# TauryCurrentSenseAmp.net
KiCad netlist of a schematic drawn in EAGLE
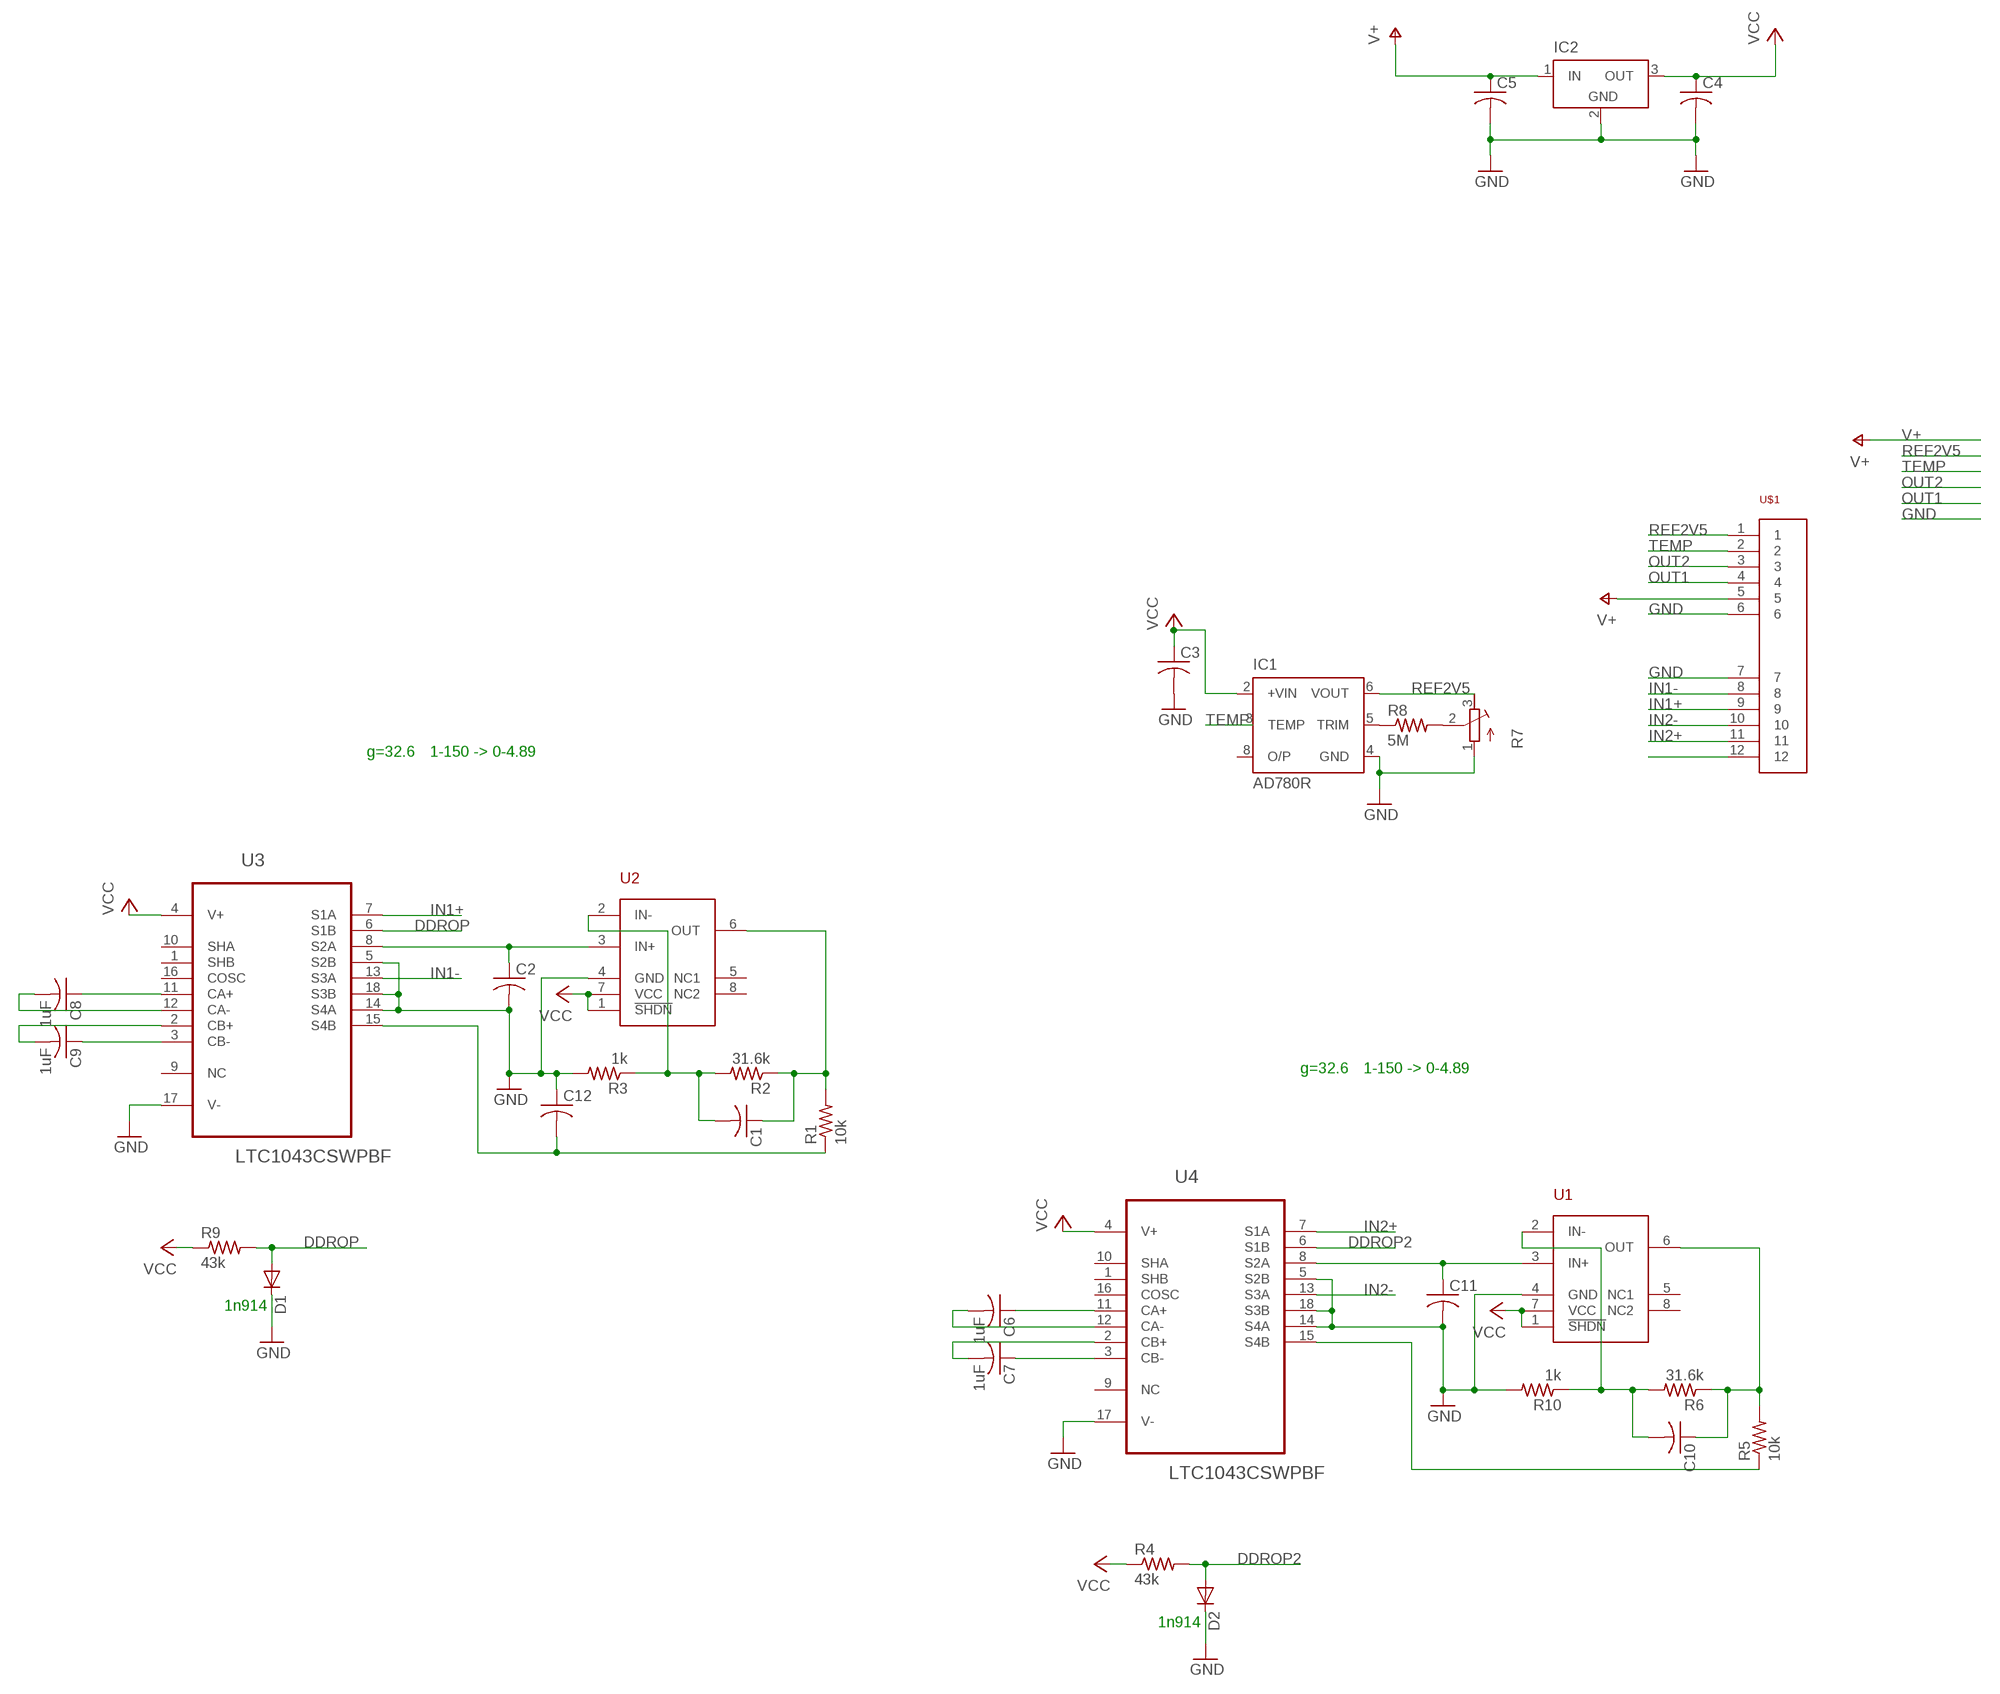
[diagram p0: schematic, sheet 1]

(export (version "E")
  (design (tool "Eeschema 10.0.6"))
  (components
    (comp (ref "C1")
      (value "C-USC0805")
      (footprint "eagle-import:C0805")
      (libsource (lib "eagle-import") (part "C-USC0805"))
    )
    (comp (ref "C2")
      (value "C-USC0805")
      (footprint "eagle-import:C0805")
      (libsource (lib "eagle-import") (part "C-USC0805"))
    )
    (comp (ref "C3")
      (value "C-USC0805")
      (footprint "eagle-import:C0805")
      (libsource (lib "eagle-import") (part "C-USC0805"))
    )
    (comp (ref "C4")
      (value "C-USC0805")
      (footprint "eagle-import:C0805")
      (libsource (lib "eagle-import") (part "C-USC0805"))
    )
    (comp (ref "C5")
      (value "C-USC0805")
      (footprint "eagle-import:C0805")
      (libsource (lib "eagle-import") (part "C-USC0805"))
    )
    (comp (ref "C6")
      (value "1uF")
      (footprint "eagle-import:C0805")
      (libsource (lib "eagle-import") (part "C-USC0805"))
    )
    (comp (ref "C7")
      (value "1uF")
      (footprint "eagle-import:C0805")
      (libsource (lib "eagle-import") (part "C-USC0805"))
    )
    (comp (ref "C8")
      (value "1uF")
      (footprint "eagle-import:C0805")
      (libsource (lib "eagle-import") (part "C-USC0805"))
    )
    (comp (ref "C9")
      (value "1uF")
      (footprint "eagle-import:C0805")
      (libsource (lib "eagle-import") (part "C-USC0805"))
    )
    (comp (ref "C10")
      (value "C-USC0805")
      (footprint "eagle-import:C0805")
      (libsource (lib "eagle-import") (part "C-USC0805"))
    )
    (comp (ref "C11")
      (value "C-USC0805")
      (footprint "eagle-import:C0805")
      (libsource (lib "eagle-import") (part "C-USC0805"))
    )
    (comp (ref "C12")
      (value "C-USC0805")
      (footprint "eagle-import:C0805")
      (libsource (lib "eagle-import") (part "C-USC0805"))
    )
    (comp (ref "D1")
      (value "DIODE-SOD323-R")
      (footprint "eagle-import:SOD323-R")
      (libsource (lib "eagle-import") (part "DIODE-SOD323-R"))
    )
    (comp (ref "D2")
      (value "DIODE-SOD523")
      (footprint "eagle-import:SOD523")
      (libsource (lib "eagle-import") (part "DIODE-SOD523"))
    )
    (comp (ref "IC1")
      (value "AD780R")
      (footprint "eagle-import:SO8")
      (fields (field (name "MPN") "AD780BRZ-REEL"))
      (libsource (lib "eagle-import") (part "AD780R"))
    )
    (comp (ref "IC2")
      (value "LT1129CST5")
      (footprint "eagle-import:SOT223")
      (fields (field (name "MPN") "LT1129CST-5#PBF"))
      (libsource (lib "eagle-import") (part "LT1129CST5"))
    )
    (comp (ref "R1")
      (value "10k")
      (footprint "eagle-import:R0805")
      (libsource (lib "eagle-import") (part "R-US_R0805"))
    )
    (comp (ref "R2")
      (value "31.6k")
      (footprint "eagle-import:R0805")
      (libsource (lib "eagle-import") (part "R-US_R0805"))
    )
    (comp (ref "R3")
      (value "1k")
      (footprint "eagle-import:R0805")
      (libsource (lib "eagle-import") (part "R-US_R0805"))
    )
    (comp (ref "R4")
      (value "43k")
      (footprint "eagle-import:R0805")
      (libsource (lib "eagle-import") (part "R-US_R0805"))
    )
    (comp (ref "R5")
      (value "10k")
      (footprint "eagle-import:R0805")
      (libsource (lib "eagle-import") (part "R-US_R0805"))
    )
    (comp (ref "R6")
      (value "31.6k")
      (footprint "eagle-import:R0805")
      (libsource (lib "eagle-import") (part "R-US_R0805"))
    )
    (comp (ref "R7")
      (value "R-TRIMM5W")
      (footprint "eagle-import:RTRIM5W")
      (libsource (lib "eagle-import") (part "R-TRIMM5W"))
    )
    (comp (ref "R8")
      (value "5M")
      (footprint "eagle-import:R0805")
      (libsource (lib "eagle-import") (part "R-US_R0805"))
    )
    (comp (ref "R9")
      (value "43k")
      (footprint "eagle-import:R0805")
      (libsource (lib "eagle-import") (part "R-US_R0805"))
    )
    (comp (ref "R10")
      (value "1k")
      (footprint "eagle-import:R0805")
      (libsource (lib "eagle-import") (part "R-US_R0805"))
    )
    (comp (ref "U$1")
      (value "DMB-4770")
      (footprint "eagle-import:DMB-4770-PCB")
      (libsource (lib "eagle-import") (part "DMB-4770"))
    )
    (comp (ref "U1")
      (value "MAX4239")
      (footprint "eagle-import:SO8")
      (libsource (lib "eagle-import") (part "MAX4239"))
    )
    (comp (ref "U2")
      (value "MAX4239")
      (footprint "eagle-import:SO8")
      (libsource (lib "eagle-import") (part "MAX4239"))
    )
    (comp (ref "U3")
      (value "LTC1043CSWPBF")
      (footprint "eagle-import:SOIC127P1032X264-18N")
      (fields (field (name "MPN") "LTC1043CSW#PBF"))
      (libsource (lib "eagle-import") (part "LTC1043CSWPBF"))
    )
    (comp (ref "U4")
      (value "LTC1043CSWPBF")
      (footprint "eagle-import:SOIC127P1032X264-18N")
      (fields (field (name "MPN") "LTC1043CSW#PBF"))
      (libsource (lib "eagle-import") (part "LTC1043CSWPBF"))
    )
  )
  (nets
    (net (code "1") (name "/DDROP") (class "Default")
      (node (ref "D1") (pin "A") (pinfunction "A_A") (pintype "passive"))
      (node (ref "R9") (pin "2") (pinfunction "2_2") (pintype "passive"))
      (node (ref "U3") (pin "6") (pinfunction "S1B_6") (pintype "passive"))
    )
    (net (code "2") (name "/DDROP2") (class "Default")
      (node (ref "D2") (pin "A") (pinfunction "A_A") (pintype "passive"))
      (node (ref "R4") (pin "2") (pinfunction "2_2") (pintype "passive"))
      (node (ref "U4") (pin "6") (pinfunction "S1B_6") (pintype "passive"))
    )
    (net (code "3") (name "/IN1+") (class "Default")
      (node (ref "U$1") (pin "9") (pinfunction "9_9") (pintype "bidirectional"))
      (node (ref "U3") (pin "7") (pinfunction "S1A_7") (pintype "passive"))
    )
    (net (code "4") (name "/IN1-") (class "Default")
      (node (ref "U$1") (pin "8") (pinfunction "8_8") (pintype "bidirectional"))
      (node (ref "U3") (pin "13") (pinfunction "S3A_13") (pintype "passive"))
    )
    (net (code "5") (name "/IN2+") (class "Default")
      (node (ref "U$1") (pin "11") (pinfunction "11_11") (pintype "bidirectional"))
      (node (ref "U4") (pin "7") (pinfunction "S1A_7") (pintype "passive"))
    )
    (net (code "6") (name "/IN2-") (class "Default")
      (node (ref "U$1") (pin "10") (pinfunction "10_10") (pintype "bidirectional"))
      (node (ref "U4") (pin "13") (pinfunction "S3A_13") (pintype "passive"))
    )
    (net (code "7") (name "/OUT1") (class "Default")
      (node (ref "C1") (pin "1") (pinfunction "1_1") (pintype "passive"))
      (node (ref "R1") (pin "2") (pinfunction "2_2") (pintype "passive"))
      (node (ref "R2") (pin "1") (pinfunction "1_1") (pintype "passive"))
      (node (ref "U$1") (pin "4") (pinfunction "4_4") (pintype "bidirectional"))
      (node (ref "U2") (pin "6") (pinfunction "OUT_6") (pintype "bidirectional"))
    )
    (net (code "8") (name "/OUT2") (class "Default")
      (node (ref "C10") (pin "1") (pinfunction "1_1") (pintype "passive"))
      (node (ref "R5") (pin "2") (pinfunction "2_2") (pintype "passive"))
      (node (ref "R6") (pin "1") (pinfunction "1_1") (pintype "passive"))
      (node (ref "U$1") (pin "3") (pinfunction "3_3") (pintype "bidirectional"))
      (node (ref "U1") (pin "6") (pinfunction "OUT_6") (pintype "bidirectional"))
    )
    (net (code "9") (name "/REF2V5") (class "Default")
      (node (ref "IC1") (pin "6") (pinfunction "VOUT_6") (pintype "input"))
      (node (ref "R7") (pin "3") (pinfunction "E_3") (pintype "passive"))
      (node (ref "U$1") (pin "1") (pinfunction "1_1") (pintype "bidirectional"))
    )
    (net (code "10") (name "/TEMP") (class "Default")
      (node (ref "IC1") (pin "3") (pinfunction "TEMP_3") (pintype "input"))
      (node (ref "U$1") (pin "2") (pinfunction "2_2") (pintype "bidirectional"))
    )
    (net (code "11") (name "GND") (class "Default")
      (node (ref "C11") (pin "2") (pinfunction "2_2") (pintype "passive"))
      (node (ref "C12") (pin "1") (pinfunction "1_1") (pintype "passive"))
      (node (ref "C2") (pin "2") (pinfunction "2_2") (pintype "passive"))
      (node (ref "C3") (pin "2") (pinfunction "2_2") (pintype "passive"))
      (node (ref "C4") (pin "2") (pinfunction "2_2") (pintype "passive"))
      (node (ref "C5") (pin "2") (pinfunction "2_2") (pintype "passive"))
      (node (ref "D1") (pin "C") (pinfunction "C_C") (pintype "passive"))
      (node (ref "D2") (pin "C") (pinfunction "C_C") (pintype "passive"))
      (node (ref "IC1") (pin "4") (pinfunction "GND_4") (pintype "power_in"))
      (node (ref "IC2") (pin "2") (pinfunction "GND_2") (pintype "power_in"))
      (node (ref "R10") (pin "2") (pinfunction "2_2") (pintype "passive"))
      (node (ref "R3") (pin "2") (pinfunction "2_2") (pintype "passive"))
      (node (ref "R7") (pin "1") (pinfunction "A_1") (pintype "passive"))
      (node (ref "U$1") (pin "6") (pinfunction "6_6") (pintype "bidirectional"))
      (node (ref "U$1") (pin "7") (pinfunction "7_7") (pintype "bidirectional"))
      (node (ref "U1") (pin "4") (pinfunction "GND_4") (pintype "bidirectional"))
      (node (ref "U2") (pin "4") (pinfunction "GND_4") (pintype "bidirectional"))
      (node (ref "U3") (pin "14") (pinfunction "S4A_14") (pintype "passive"))
      (node (ref "U3") (pin "17") (pinfunction "V-_17") (pintype "power_in"))
      (node (ref "U3") (pin "18") (pinfunction "S3B_18") (pintype "passive"))
      (node (ref "U3") (pin "5") (pinfunction "S2B_5") (pintype "passive"))
      (node (ref "U4") (pin "14") (pinfunction "S4A_14") (pintype "passive"))
      (node (ref "U4") (pin "17") (pinfunction "V-_17") (pintype "power_in"))
      (node (ref "U4") (pin "18") (pinfunction "S3B_18") (pintype "passive"))
      (node (ref "U4") (pin "5") (pinfunction "S2B_5") (pintype "passive"))
    )
    (net (code "12") (name "Net-(IC1-TRIM)") (class "Default")
      (node (ref "IC1") (pin "5") (pinfunction "TRIM_5") (pintype "input"))
      (node (ref "R8") (pin "1") (pinfunction "1_1") (pintype "passive"))
    )
    (net (code "13") (name "Net-(R7-S)") (class "Default")
      (node (ref "R7") (pin "2") (pinfunction "S_2") (pintype "passive"))
      (node (ref "R8") (pin "2") (pinfunction "2_2") (pintype "passive"))
    )
    (net (code "14") (name "Net-(U1-IN+)") (class "Default")
      (node (ref "C11") (pin "1") (pinfunction "1_1") (pintype "passive"))
      (node (ref "U1") (pin "3") (pinfunction "IN+_3") (pintype "bidirectional"))
      (node (ref "U4") (pin "8") (pinfunction "S2A_8") (pintype "passive"))
    )
    (net (code "15") (name "Net-(U1-IN-)") (class "Default")
      (node (ref "C10") (pin "2") (pinfunction "2_2") (pintype "passive"))
      (node (ref "R10") (pin "1") (pinfunction "1_1") (pintype "passive"))
      (node (ref "R6") (pin "2") (pinfunction "2_2") (pintype "passive"))
      (node (ref "U1") (pin "2") (pinfunction "IN-_2") (pintype "bidirectional"))
    )
    (net (code "16") (name "Net-(U2-IN+)") (class "Default")
      (node (ref "C2") (pin "1") (pinfunction "1_1") (pintype "passive"))
      (node (ref "U2") (pin "3") (pinfunction "IN+_3") (pintype "bidirectional"))
      (node (ref "U3") (pin "8") (pinfunction "S2A_8") (pintype "passive"))
    )
    (net (code "17") (name "Net-(U2-IN-)") (class "Default")
      (node (ref "C1") (pin "2") (pinfunction "2_2") (pintype "passive"))
      (node (ref "R2") (pin "2") (pinfunction "2_2") (pintype "passive"))
      (node (ref "R3") (pin "1") (pinfunction "1_1") (pintype "passive"))
      (node (ref "U2") (pin "2") (pinfunction "IN-_2") (pintype "bidirectional"))
    )
    (net (code "18") (name "Net-(U3-CA+)") (class "Default")
      (node (ref "C8") (pin "1") (pinfunction "1_1") (pintype "passive"))
      (node (ref "U3") (pin "11") (pinfunction "CA+_11") (pintype "passive"))
    )
    (net (code "19") (name "Net-(U3-CA-)") (class "Default")
      (node (ref "C8") (pin "2") (pinfunction "2_2") (pintype "passive"))
      (node (ref "U3") (pin "12") (pinfunction "CA-_12") (pintype "passive"))
    )
    (net (code "20") (name "Net-(U3-CB+)") (class "Default")
      (node (ref "C9") (pin "2") (pinfunction "2_2") (pintype "passive"))
      (node (ref "U3") (pin "2") (pinfunction "CB+_2") (pintype "passive"))
    )
    (net (code "21") (name "Net-(U3-CB-)") (class "Default")
      (node (ref "C9") (pin "1") (pinfunction "1_1") (pintype "passive"))
      (node (ref "U3") (pin "3") (pinfunction "CB-_3") (pintype "passive"))
    )
    (net (code "22") (name "Net-(U3-S4B)") (class "Default")
      (node (ref "C12") (pin "2") (pinfunction "2_2") (pintype "passive"))
      (node (ref "R1") (pin "1") (pinfunction "1_1") (pintype "passive"))
      (node (ref "U3") (pin "15") (pinfunction "S4B_15") (pintype "passive"))
    )
    (net (code "23") (name "Net-(U4-CA+)") (class "Default")
      (node (ref "C6") (pin "1") (pinfunction "1_1") (pintype "passive"))
      (node (ref "U4") (pin "11") (pinfunction "CA+_11") (pintype "passive"))
    )
    (net (code "24") (name "Net-(U4-CA-)") (class "Default")
      (node (ref "C6") (pin "2") (pinfunction "2_2") (pintype "passive"))
      (node (ref "U4") (pin "12") (pinfunction "CA-_12") (pintype "passive"))
    )
    (net (code "25") (name "Net-(U4-CB+)") (class "Default")
      (node (ref "C7") (pin "2") (pinfunction "2_2") (pintype "passive"))
      (node (ref "U4") (pin "2") (pinfunction "CB+_2") (pintype "passive"))
    )
    (net (code "26") (name "Net-(U4-CB-)") (class "Default")
      (node (ref "C7") (pin "1") (pinfunction "1_1") (pintype "passive"))
      (node (ref "U4") (pin "3") (pinfunction "CB-_3") (pintype "passive"))
    )
    (net (code "27") (name "Net-(U4-S4B)") (class "Default")
      (node (ref "R5") (pin "1") (pinfunction "1_1") (pintype "passive"))
      (node (ref "U4") (pin "15") (pinfunction "S4B_15") (pintype "passive"))
    )
    (net (code "28") (name "V+") (class "Default")
      (node (ref "C5") (pin "1") (pinfunction "1_1") (pintype "passive"))
      (node (ref "IC2") (pin "1") (pinfunction "IN_1") (pintype "input"))
      (node (ref "U$1") (pin "5") (pinfunction "5_5") (pintype "bidirectional"))
    )
    (net (code "29") (name "VCC") (class "Default")
      (node (ref "C3") (pin "1") (pinfunction "1_1") (pintype "passive"))
      (node (ref "C4") (pin "1") (pinfunction "1_1") (pintype "passive"))
      (node (ref "IC1") (pin "2") (pinfunction "+VIN_2") (pintype "input"))
      (node (ref "IC2") (pin "3") (pinfunction "OUT_3") (pintype "output"))
      (node (ref "R4") (pin "1") (pinfunction "1_1") (pintype "passive"))
      (node (ref "R9") (pin "1") (pinfunction "1_1") (pintype "passive"))
      (node (ref "U1") (pin "1") (pinfunction "~{SHDN}_1") (pintype "bidirectional"))
      (node (ref "U1") (pin "7") (pinfunction "VCC_7") (pintype "bidirectional"))
      (node (ref "U2") (pin "1") (pinfunction "~{SHDN}_1") (pintype "bidirectional"))
      (node (ref "U2") (pin "7") (pinfunction "VCC_7") (pintype "bidirectional"))
      (node (ref "U3") (pin "4") (pinfunction "V+_4") (pintype "power_in"))
      (node (ref "U4") (pin "4") (pinfunction "V+_4") (pintype "power_in"))
    )
    (net (code "30") (name "unconnected-(IC1-O{slash}P-Pad8)") (class "Default")
      (node (ref "IC1") (pin "8") (pinfunction "O/P_8") (pintype "passive"))
    )
    (net (code "31") (name "unconnected-(U$1-Pad12)") (class "Default")
      (node (ref "U$1") (pin "12") (pinfunction "12_12") (pintype "bidirectional"))
    )
    (net (code "32") (name "unconnected-(U1-NC1-Pad5)") (class "Default")
      (node (ref "U1") (pin "5") (pinfunction "NC1_5") (pintype "bidirectional"))
    )
    (net (code "33") (name "unconnected-(U1-NC2-Pad8)") (class "Default")
      (node (ref "U1") (pin "8") (pinfunction "NC2_8") (pintype "bidirectional"))
    )
    (net (code "34") (name "unconnected-(U2-NC1-Pad5)") (class "Default")
      (node (ref "U2") (pin "5") (pinfunction "NC1_5") (pintype "bidirectional"))
    )
    (net (code "35") (name "unconnected-(U2-NC2-Pad8)") (class "Default")
      (node (ref "U2") (pin "8") (pinfunction "NC2_8") (pintype "bidirectional"))
    )
    (net (code "36") (name "unconnected-(U3-COSC-Pad16)") (class "Default")
      (node (ref "U3") (pin "16") (pinfunction "COSC_16") (pintype "passive"))
    )
    (net (code "37") (name "unconnected-(U3-NC-Pad9)") (class "Default")
      (node (ref "U3") (pin "9") (pinfunction "NC_9") (pintype "no_connect"))
    )
    (net (code "38") (name "unconnected-(U3-SHA-Pad10)") (class "Default")
      (node (ref "U3") (pin "10") (pinfunction "SHA_10") (pintype "passive"))
    )
    (net (code "39") (name "unconnected-(U3-SHB-Pad1)") (class "Default")
      (node (ref "U3") (pin "1") (pinfunction "SHB_1") (pintype "passive"))
    )
    (net (code "40") (name "unconnected-(U4-COSC-Pad16)") (class "Default")
      (node (ref "U4") (pin "16") (pinfunction "COSC_16") (pintype "passive"))
    )
    (net (code "41") (name "unconnected-(U4-NC-Pad9)") (class "Default")
      (node (ref "U4") (pin "9") (pinfunction "NC_9") (pintype "no_connect"))
    )
    (net (code "42") (name "unconnected-(U4-SHA-Pad10)") (class "Default")
      (node (ref "U4") (pin "10") (pinfunction "SHA_10") (pintype "passive"))
    )
    (net (code "43") (name "unconnected-(U4-SHB-Pad1)") (class "Default")
      (node (ref "U4") (pin "1") (pinfunction "SHB_1") (pintype "passive"))
    )
  )
)
